# Adafruit_5x5_NeoPixel_Grid_BFF.net
KiCad netlist of a schematic drawn in EAGLE
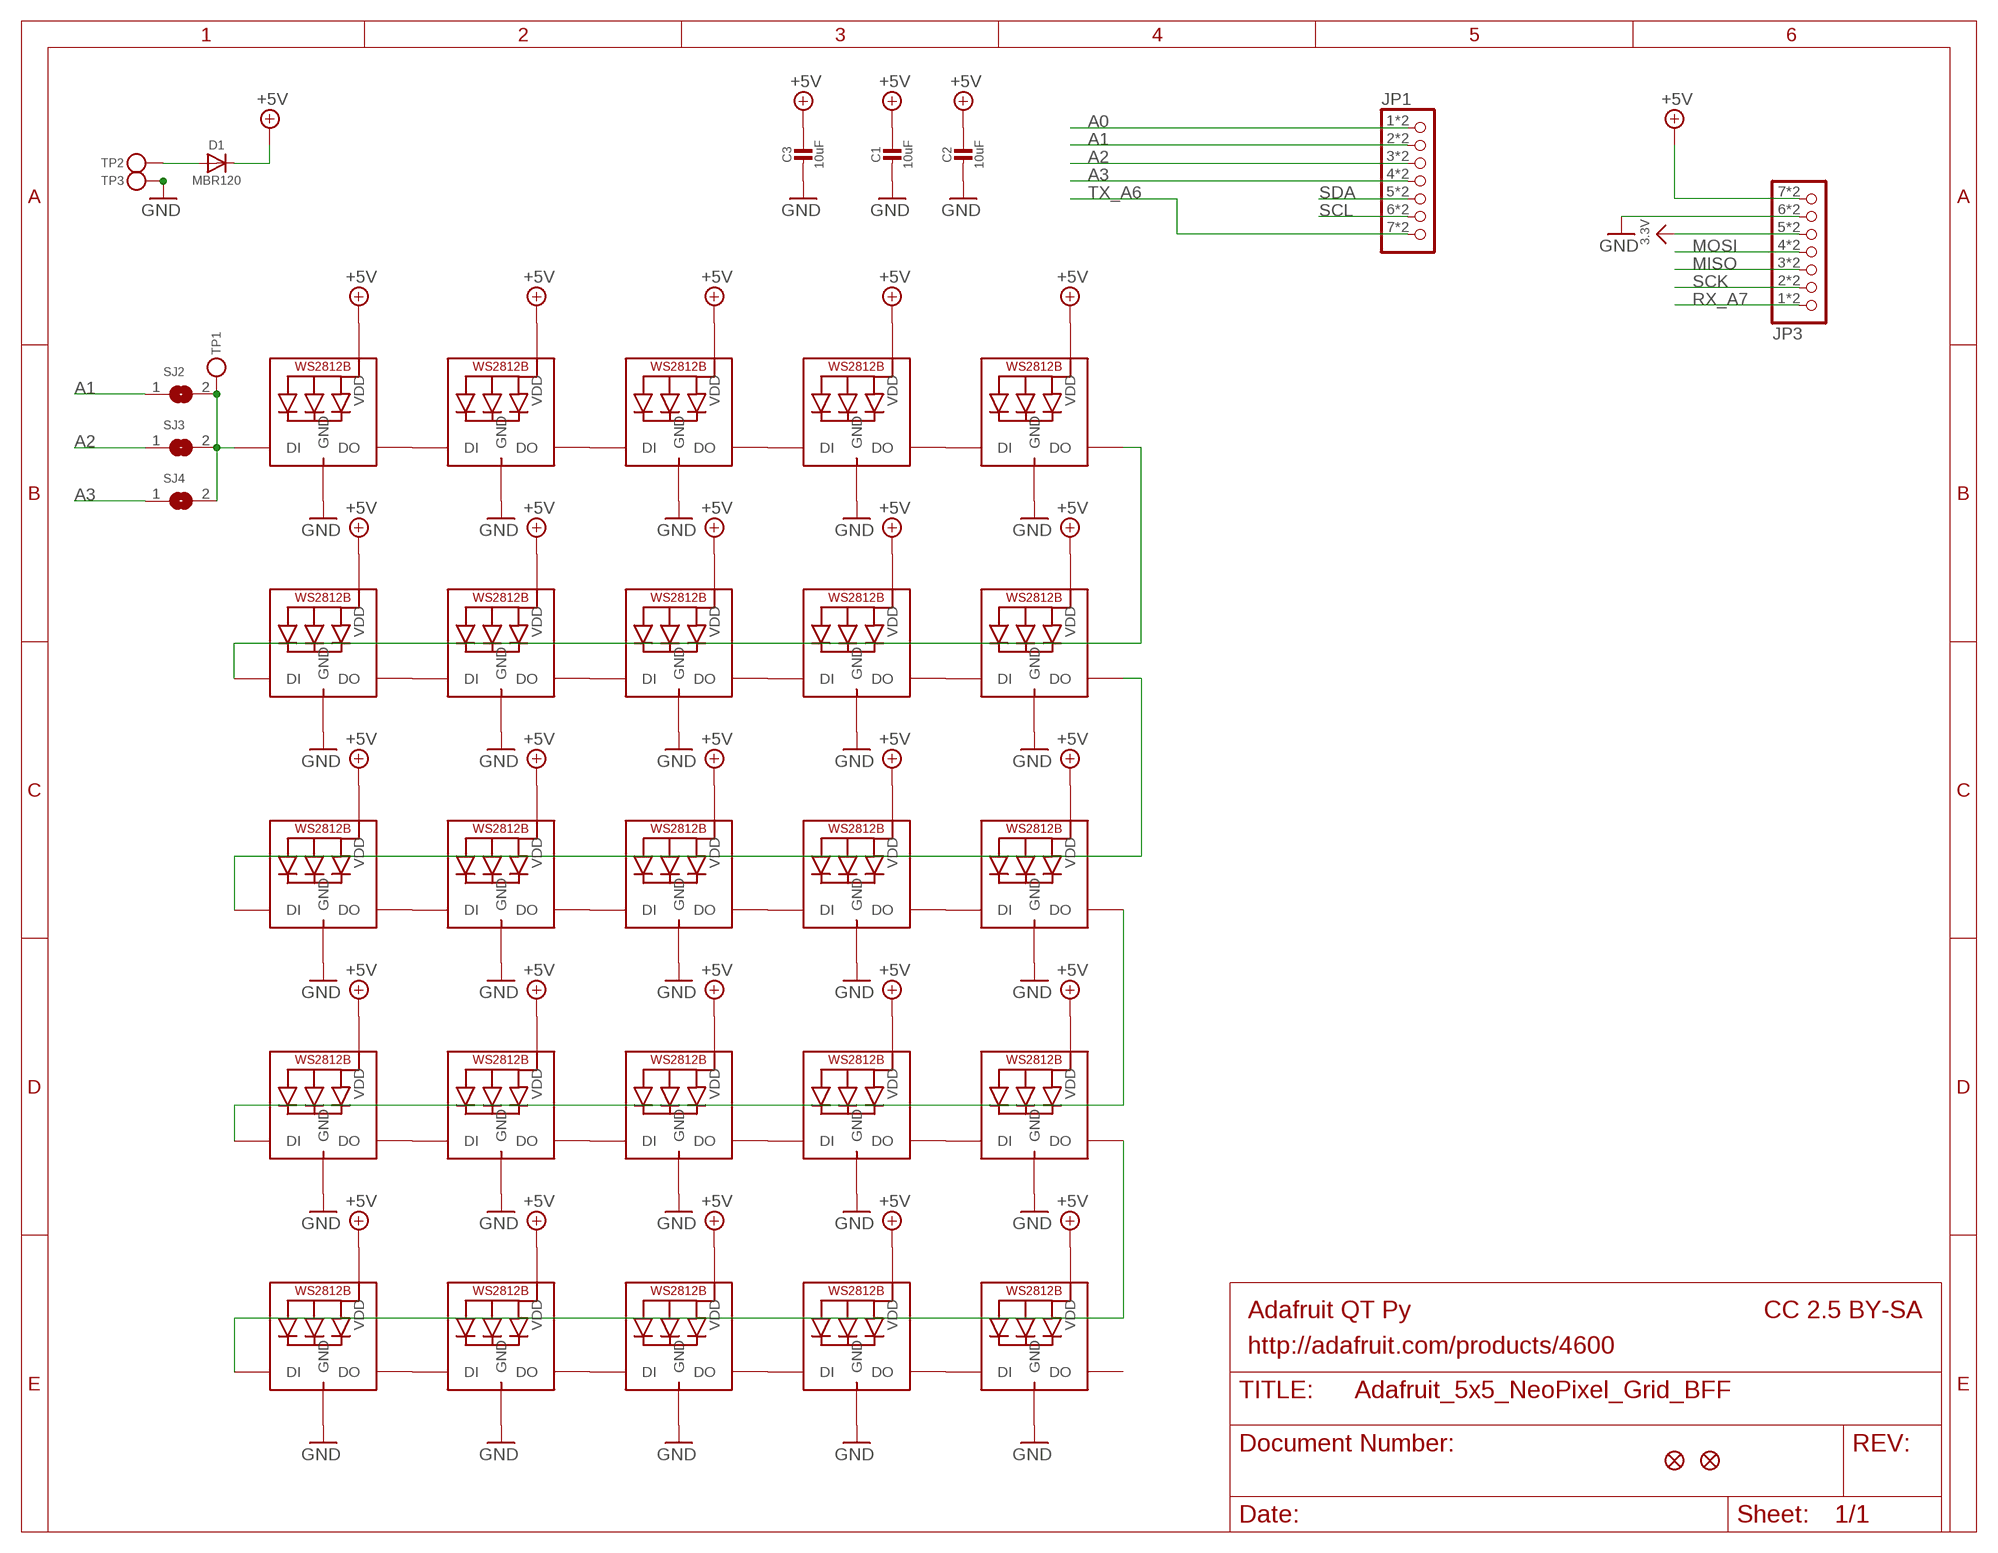
[diagram p0: schematic, sheet 1]

(export (version "E")
  (design (tool "Eeschema 10.0.6"))
  (components
    (comp (ref "C1")
      (value "10uF")
      (footprint "eagle-import:0603-NO")
      (libsource (lib "eagle-import") (part "CAP_CERAMIC0603_NO"))
    )
    (comp (ref "C2")
      (value "10uF")
      (footprint "eagle-import:0603-NO")
      (libsource (lib "eagle-import") (part "CAP_CERAMIC0603_NO"))
    )
    (comp (ref "C3")
      (value "10uF")
      (footprint "eagle-import:0603-NO")
      (libsource (lib "eagle-import") (part "CAP_CERAMIC0603_NO"))
    )
    (comp (ref "D1")
      (value "MBR120")
      (footprint "eagle-import:SOD-123")
      (libsource (lib "eagle-import") (part "DIODESOD-123"))
    )
    (comp (ref "JP1")
      (value "HEADER-1X7_CASTEL")
      (footprint "eagle-import:1X07_CASTEL")
      (libsource (lib "eagle-import") (part "HEADER-1X7_CASTEL"))
    )
    (comp (ref "JP3")
      (value "HEADER-1X7_CASTEL")
      (footprint "eagle-import:1X07_CASTEL")
      (libsource (lib "eagle-import") (part "HEADER-1X7_CASTEL"))
    )
    (comp (ref "LED1")
      (value "WS2812B_SK6805_1515")
      (footprint "eagle-import:SK6805_1515")
      (libsource (lib "eagle-import") (part "WS2812B_SK6805_1515"))
    )
    (comp (ref "LED2")
      (value "WS2812B_SK6805_1515")
      (footprint "eagle-import:SK6805_1515")
      (libsource (lib "eagle-import") (part "WS2812B_SK6805_1515"))
    )
    (comp (ref "LED3")
      (value "WS2812B_SK6805_1515")
      (footprint "eagle-import:SK6805_1515")
      (libsource (lib "eagle-import") (part "WS2812B_SK6805_1515"))
    )
    (comp (ref "LED4")
      (value "WS2812B_SK6805_1515")
      (footprint "eagle-import:SK6805_1515")
      (libsource (lib "eagle-import") (part "WS2812B_SK6805_1515"))
    )
    (comp (ref "LED5")
      (value "WS2812B_SK6805_1515")
      (footprint "eagle-import:SK6805_1515")
      (libsource (lib "eagle-import") (part "WS2812B_SK6805_1515"))
    )
    (comp (ref "LED6")
      (value "WS2812B_SK6805_1515")
      (footprint "eagle-import:SK6805_1515")
      (libsource (lib "eagle-import") (part "WS2812B_SK6805_1515"))
    )
    (comp (ref "LED7")
      (value "WS2812B_SK6805_1515")
      (footprint "eagle-import:SK6805_1515")
      (libsource (lib "eagle-import") (part "WS2812B_SK6805_1515"))
    )
    (comp (ref "LED8")
      (value "WS2812B_SK6805_1515")
      (footprint "eagle-import:SK6805_1515")
      (libsource (lib "eagle-import") (part "WS2812B_SK6805_1515"))
    )
    (comp (ref "LED9")
      (value "WS2812B_SK6805_1515")
      (footprint "eagle-import:SK6805_1515")
      (libsource (lib "eagle-import") (part "WS2812B_SK6805_1515"))
    )
    (comp (ref "LED10")
      (value "WS2812B_SK6805_1515")
      (footprint "eagle-import:SK6805_1515")
      (libsource (lib "eagle-import") (part "WS2812B_SK6805_1515"))
    )
    (comp (ref "LED11")
      (value "WS2812B_SK6805_1515")
      (footprint "eagle-import:SK6805_1515")
      (libsource (lib "eagle-import") (part "WS2812B_SK6805_1515"))
    )
    (comp (ref "LED12")
      (value "WS2812B_SK6805_1515")
      (footprint "eagle-import:SK6805_1515")
      (libsource (lib "eagle-import") (part "WS2812B_SK6805_1515"))
    )
    (comp (ref "LED13")
      (value "WS2812B_SK6805_1515")
      (footprint "eagle-import:SK6805_1515")
      (libsource (lib "eagle-import") (part "WS2812B_SK6805_1515"))
    )
    (comp (ref "LED14")
      (value "WS2812B_SK6805_1515")
      (footprint "eagle-import:SK6805_1515")
      (libsource (lib "eagle-import") (part "WS2812B_SK6805_1515"))
    )
    (comp (ref "LED15")
      (value "WS2812B_SK6805_1515")
      (footprint "eagle-import:SK6805_1515")
      (libsource (lib "eagle-import") (part "WS2812B_SK6805_1515"))
    )
    (comp (ref "LED16")
      (value "WS2812B_SK6805_1515")
      (footprint "eagle-import:SK6805_1515")
      (libsource (lib "eagle-import") (part "WS2812B_SK6805_1515"))
    )
    (comp (ref "LED17")
      (value "WS2812B_SK6805_1515")
      (footprint "eagle-import:SK6805_1515")
      (libsource (lib "eagle-import") (part "WS2812B_SK6805_1515"))
    )
    (comp (ref "LED18")
      (value "WS2812B_SK6805_1515")
      (footprint "eagle-import:SK6805_1515")
      (libsource (lib "eagle-import") (part "WS2812B_SK6805_1515"))
    )
    (comp (ref "LED19")
      (value "WS2812B_SK6805_1515")
      (footprint "eagle-import:SK6805_1515")
      (libsource (lib "eagle-import") (part "WS2812B_SK6805_1515"))
    )
    (comp (ref "LED20")
      (value "WS2812B_SK6805_1515")
      (footprint "eagle-import:SK6805_1515")
      (libsource (lib "eagle-import") (part "WS2812B_SK6805_1515"))
    )
    (comp (ref "LED21")
      (value "WS2812B_SK6805_1515")
      (footprint "eagle-import:SK6805_1515")
      (libsource (lib "eagle-import") (part "WS2812B_SK6805_1515"))
    )
    (comp (ref "LED22")
      (value "WS2812B_SK6805_1515")
      (footprint "eagle-import:SK6805_1515")
      (libsource (lib "eagle-import") (part "WS2812B_SK6805_1515"))
    )
    (comp (ref "LED23")
      (value "WS2812B_SK6805_1515")
      (footprint "eagle-import:SK6805_1515")
      (libsource (lib "eagle-import") (part "WS2812B_SK6805_1515"))
    )
    (comp (ref "LED24")
      (value "WS2812B_SK6805_1515")
      (footprint "eagle-import:SK6805_1515")
      (libsource (lib "eagle-import") (part "WS2812B_SK6805_1515"))
    )
    (comp (ref "LED25")
      (value "WS2812B_SK6805_1515")
      (footprint "eagle-import:SK6805_1515")
      (libsource (lib "eagle-import") (part "WS2812B_SK6805_1515"))
    )
    (comp (ref "SJ2")
      (value "SOLDERJUMPER")
      (footprint "eagle-import:SOLDERJUMPER_ARROW_NOPASTE")
      (libsource (lib "eagle-import") (part "SOLDERJUMPER"))
    )
    (comp (ref "SJ3")
      (value "SOLDERJUMPER")
      (footprint "eagle-import:SOLDERJUMPER_ARROW_NOPASTE")
      (libsource (lib "eagle-import") (part "SOLDERJUMPER"))
    )
    (comp (ref "SJ4")
      (value "SOLDERJUMPERCLOSED")
      (footprint "eagle-import:SOLDERJUMPER_CLOSEDWIRE")
      (libsource (lib "eagle-import") (part "SOLDERJUMPERCLOSED"))
    )
    (comp (ref "TP1")
      (value "TESTPOINT_1X3")
      (footprint "eagle-import:TESTPOINT_RECT_1X3MM")
      (libsource (lib "eagle-import") (part "TESTPOINT_1X3"))
    )
    (comp (ref "TP2")
      (value "TESTPOINT_PLUS13")
      (footprint "eagle-import:TESTPOINT_PLUS_1X3MM")
      (libsource (lib "eagle-import") (part "TESTPOINT_PLUS13"))
    )
    (comp (ref "TP3")
      (value "TESTPOINT_MINUS")
      (footprint "eagle-import:TESTPOINT_MINUS_1X3MM")
      (libsource (lib "eagle-import") (part "TESTPOINT_MINUS"))
    )
    (comp (ref "U$6")
      (value "FIDUCIAL_1MM")
      (footprint "eagle-import:FIDUCIAL_1MM")
      (libsource (lib "eagle-import") (part "FIDUCIAL_1MM"))
    )
    (comp (ref "U$8")
      (value "FIDUCIAL_1MM")
      (footprint "eagle-import:FIDUCIAL_1MM")
      (libsource (lib "eagle-import") (part "FIDUCIAL_1MM"))
    )
  )
  (nets
    (net (code "1") (name "+5V") (class "Default")
      (node (ref "C1") (pin "1") (pinfunction "1_1") (pintype "passive"))
      (node (ref "C2") (pin "1") (pinfunction "1_1") (pintype "passive"))
      (node (ref "C3") (pin "1") (pinfunction "1_1") (pintype "passive"))
      (node (ref "D1") (pin "C") (pinfunction "C_C") (pintype "passive"))
      (node (ref "JP3") (pin "7") (pinfunction "7_7") (pintype "passive"))
      (node (ref "JP3") (pin "7C") (pinfunction "7_7C") (pintype "passive"))
      (node (ref "LED1") (pin "2") (pinfunction "VDD_2") (pintype "power_in"))
      (node (ref "LED10") (pin "2") (pinfunction "VDD_2") (pintype "power_in"))
      (node (ref "LED11") (pin "2") (pinfunction "VDD_2") (pintype "power_in"))
      (node (ref "LED12") (pin "2") (pinfunction "VDD_2") (pintype "power_in"))
      (node (ref "LED13") (pin "2") (pinfunction "VDD_2") (pintype "power_in"))
      (node (ref "LED14") (pin "2") (pinfunction "VDD_2") (pintype "power_in"))
      (node (ref "LED15") (pin "2") (pinfunction "VDD_2") (pintype "power_in"))
      (node (ref "LED16") (pin "2") (pinfunction "VDD_2") (pintype "power_in"))
      (node (ref "LED17") (pin "2") (pinfunction "VDD_2") (pintype "power_in"))
      (node (ref "LED18") (pin "2") (pinfunction "VDD_2") (pintype "power_in"))
      (node (ref "LED19") (pin "2") (pinfunction "VDD_2") (pintype "power_in"))
      (node (ref "LED2") (pin "2") (pinfunction "VDD_2") (pintype "power_in"))
      (node (ref "LED20") (pin "2") (pinfunction "VDD_2") (pintype "power_in"))
      (node (ref "LED21") (pin "2") (pinfunction "VDD_2") (pintype "power_in"))
      (node (ref "LED22") (pin "2") (pinfunction "VDD_2") (pintype "power_in"))
      (node (ref "LED23") (pin "2") (pinfunction "VDD_2") (pintype "power_in"))
      (node (ref "LED24") (pin "2") (pinfunction "VDD_2") (pintype "power_in"))
      (node (ref "LED25") (pin "2") (pinfunction "VDD_2") (pintype "power_in"))
      (node (ref "LED3") (pin "2") (pinfunction "VDD_2") (pintype "power_in"))
      (node (ref "LED4") (pin "2") (pinfunction "VDD_2") (pintype "power_in"))
      (node (ref "LED5") (pin "2") (pinfunction "VDD_2") (pintype "power_in"))
      (node (ref "LED6") (pin "2") (pinfunction "VDD_2") (pintype "power_in"))
      (node (ref "LED7") (pin "2") (pinfunction "VDD_2") (pintype "power_in"))
      (node (ref "LED8") (pin "2") (pinfunction "VDD_2") (pintype "power_in"))
      (node (ref "LED9") (pin "2") (pinfunction "VDD_2") (pintype "power_in"))
    )
    (net (code "2") (name "/A0") (class "Default")
      (node (ref "JP1") (pin "1") (pinfunction "1_1") (pintype "passive"))
      (node (ref "JP1") (pin "1C") (pinfunction "1_1C") (pintype "passive"))
    )
    (net (code "3") (name "/A1") (class "Default")
      (node (ref "JP1") (pin "2") (pinfunction "2_2") (pintype "passive"))
      (node (ref "JP1") (pin "2C") (pinfunction "2_2C") (pintype "passive"))
      (node (ref "SJ2") (pin "1") (pinfunction "1_1") (pintype "passive"))
    )
    (net (code "4") (name "/A2") (class "Default")
      (node (ref "JP1") (pin "3") (pinfunction "3_3") (pintype "passive"))
      (node (ref "JP1") (pin "3C") (pinfunction "3_3C") (pintype "passive"))
      (node (ref "SJ3") (pin "1") (pinfunction "1_1") (pintype "passive"))
    )
    (net (code "5") (name "/A3") (class "Default")
      (node (ref "JP1") (pin "4") (pinfunction "4_4") (pintype "passive"))
      (node (ref "JP1") (pin "4C") (pinfunction "4_4C") (pintype "passive"))
      (node (ref "SJ4") (pin "1") (pinfunction "1_1") (pintype "passive"))
    )
    (net (code "6") (name "/MISO") (class "Default")
      (node (ref "JP3") (pin "3") (pinfunction "3_3") (pintype "passive"))
      (node (ref "JP3") (pin "3C") (pinfunction "3_3C") (pintype "passive"))
    )
    (net (code "7") (name "/MOSI") (class "Default")
      (node (ref "JP3") (pin "4") (pinfunction "4_4") (pintype "passive"))
      (node (ref "JP3") (pin "4C") (pinfunction "4_4C") (pintype "passive"))
    )
    (net (code "8") (name "/RX_A7") (class "Default")
      (node (ref "JP3") (pin "1") (pinfunction "1_1") (pintype "passive"))
      (node (ref "JP3") (pin "1C") (pinfunction "1_1C") (pintype "passive"))
    )
    (net (code "9") (name "/SCK") (class "Default")
      (node (ref "JP3") (pin "2") (pinfunction "2_2") (pintype "passive"))
      (node (ref "JP3") (pin "2C") (pinfunction "2_2C") (pintype "passive"))
    )
    (net (code "10") (name "/SCL") (class "Default")
      (node (ref "JP1") (pin "6") (pinfunction "6_6") (pintype "passive"))
      (node (ref "JP1") (pin "6C") (pinfunction "6_6C") (pintype "passive"))
    )
    (net (code "11") (name "/SDA") (class "Default")
      (node (ref "JP1") (pin "5") (pinfunction "5_5") (pintype "passive"))
      (node (ref "JP1") (pin "5C") (pinfunction "5_5C") (pintype "passive"))
    )
    (net (code "12") (name "/TX_A6") (class "Default")
      (node (ref "JP1") (pin "7") (pinfunction "7_7") (pintype "passive"))
      (node (ref "JP1") (pin "7C") (pinfunction "7_7C") (pintype "passive"))
    )
    (net (code "13") (name "3.3V") (class "Default")
      (node (ref "JP3") (pin "5") (pinfunction "5_5") (pintype "passive"))
      (node (ref "JP3") (pin "5C") (pinfunction "5_5C") (pintype "passive"))
    )
    (net (code "14") (name "GND") (class "Default")
      (node (ref "C1") (pin "2") (pinfunction "2_2") (pintype "passive"))
      (node (ref "C2") (pin "2") (pinfunction "2_2") (pintype "passive"))
      (node (ref "C3") (pin "2") (pinfunction "2_2") (pintype "passive"))
      (node (ref "JP3") (pin "6") (pinfunction "6_6") (pintype "passive"))
      (node (ref "JP3") (pin "6C") (pinfunction "6_6C") (pintype "passive"))
      (node (ref "LED1") (pin "4") (pinfunction "GND_4") (pintype "power_in"))
      (node (ref "LED10") (pin "4") (pinfunction "GND_4") (pintype "power_in"))
      (node (ref "LED11") (pin "4") (pinfunction "GND_4") (pintype "power_in"))
      (node (ref "LED12") (pin "4") (pinfunction "GND_4") (pintype "power_in"))
      (node (ref "LED13") (pin "4") (pinfunction "GND_4") (pintype "power_in"))
      (node (ref "LED14") (pin "4") (pinfunction "GND_4") (pintype "power_in"))
      (node (ref "LED15") (pin "4") (pinfunction "GND_4") (pintype "power_in"))
      (node (ref "LED16") (pin "4") (pinfunction "GND_4") (pintype "power_in"))
      (node (ref "LED17") (pin "4") (pinfunction "GND_4") (pintype "power_in"))
      (node (ref "LED18") (pin "4") (pinfunction "GND_4") (pintype "power_in"))
      (node (ref "LED19") (pin "4") (pinfunction "GND_4") (pintype "power_in"))
      (node (ref "LED2") (pin "4") (pinfunction "GND_4") (pintype "power_in"))
      (node (ref "LED20") (pin "4") (pinfunction "GND_4") (pintype "power_in"))
      (node (ref "LED21") (pin "4") (pinfunction "GND_4") (pintype "power_in"))
      (node (ref "LED22") (pin "4") (pinfunction "GND_4") (pintype "power_in"))
      (node (ref "LED23") (pin "4") (pinfunction "GND_4") (pintype "power_in"))
      (node (ref "LED24") (pin "4") (pinfunction "GND_4") (pintype "power_in"))
      (node (ref "LED25") (pin "4") (pinfunction "GND_4") (pintype "power_in"))
      (node (ref "LED3") (pin "4") (pinfunction "GND_4") (pintype "power_in"))
      (node (ref "LED4") (pin "4") (pinfunction "GND_4") (pintype "power_in"))
      (node (ref "LED5") (pin "4") (pinfunction "GND_4") (pintype "power_in"))
      (node (ref "LED6") (pin "4") (pinfunction "GND_4") (pintype "power_in"))
      (node (ref "LED7") (pin "4") (pinfunction "GND_4") (pintype "power_in"))
      (node (ref "LED8") (pin "4") (pinfunction "GND_4") (pintype "power_in"))
      (node (ref "LED9") (pin "4") (pinfunction "GND_4") (pintype "power_in"))
      (node (ref "TP3") (pin "P$1") (pinfunction "P$1_P$1") (pintype "bidirectional"))
    )
    (net (code "15") (name "Net-(D1-PadA)") (class "Default")
      (node (ref "D1") (pin "A") (pinfunction "A_A") (pintype "passive"))
      (node (ref "TP2") (pin "P$1") (pinfunction "P$1_P$1") (pintype "bidirectional"))
    )
    (net (code "16") (name "Net-(LED1-DI)") (class "Default")
      (node (ref "LED1") (pin "1") (pinfunction "DI_1") (pintype "input"))
      (node (ref "SJ2") (pin "2") (pinfunction "2_2") (pintype "passive"))
      (node (ref "SJ3") (pin "2") (pinfunction "2_2") (pintype "passive"))
      (node (ref "SJ4") (pin "2") (pinfunction "2_2") (pintype "passive"))
      (node (ref "TP1") (pin "P$1") (pinfunction "P$1_P$1") (pintype "bidirectional"))
    )
    (net (code "17") (name "Net-(LED1-DO)") (class "Default")
      (node (ref "LED1") (pin "3") (pinfunction "DO_3") (pintype "output"))
      (node (ref "LED2") (pin "1") (pinfunction "DI_1") (pintype "input"))
    )
    (net (code "18") (name "Net-(LED2-DO)") (class "Default")
      (node (ref "LED2") (pin "3") (pinfunction "DO_3") (pintype "output"))
      (node (ref "LED3") (pin "1") (pinfunction "DI_1") (pintype "input"))
    )
    (net (code "19") (name "Net-(LED3-DO)") (class "Default")
      (node (ref "LED3") (pin "3") (pinfunction "DO_3") (pintype "output"))
      (node (ref "LED4") (pin "1") (pinfunction "DI_1") (pintype "input"))
    )
    (net (code "20") (name "Net-(LED4-DO)") (class "Default")
      (node (ref "LED4") (pin "3") (pinfunction "DO_3") (pintype "output"))
      (node (ref "LED5") (pin "1") (pinfunction "DI_1") (pintype "input"))
    )
    (net (code "21") (name "Net-(LED5-DO)") (class "Default")
      (node (ref "LED5") (pin "3") (pinfunction "DO_3") (pintype "output"))
      (node (ref "LED6") (pin "1") (pinfunction "DI_1") (pintype "input"))
    )
    (net (code "22") (name "Net-(LED6-DO)") (class "Default")
      (node (ref "LED6") (pin "3") (pinfunction "DO_3") (pintype "output"))
      (node (ref "LED7") (pin "1") (pinfunction "DI_1") (pintype "input"))
    )
    (net (code "23") (name "Net-(LED7-DO)") (class "Default")
      (node (ref "LED7") (pin "3") (pinfunction "DO_3") (pintype "output"))
      (node (ref "LED8") (pin "1") (pinfunction "DI_1") (pintype "input"))
    )
    (net (code "24") (name "Net-(LED8-DO)") (class "Default")
      (node (ref "LED8") (pin "3") (pinfunction "DO_3") (pintype "output"))
      (node (ref "LED9") (pin "1") (pinfunction "DI_1") (pintype "input"))
    )
    (net (code "25") (name "Net-(LED10-DI)") (class "Default")
      (node (ref "LED10") (pin "1") (pinfunction "DI_1") (pintype "input"))
      (node (ref "LED9") (pin "3") (pinfunction "DO_3") (pintype "output"))
    )
    (net (code "26") (name "Net-(LED10-DO)") (class "Default")
      (node (ref "LED10") (pin "3") (pinfunction "DO_3") (pintype "output"))
      (node (ref "LED11") (pin "1") (pinfunction "DI_1") (pintype "input"))
    )
    (net (code "27") (name "Net-(LED11-DO)") (class "Default")
      (node (ref "LED11") (pin "3") (pinfunction "DO_3") (pintype "output"))
      (node (ref "LED12") (pin "1") (pinfunction "DI_1") (pintype "input"))
    )
    (net (code "28") (name "Net-(LED12-DO)") (class "Default")
      (node (ref "LED12") (pin "3") (pinfunction "DO_3") (pintype "output"))
      (node (ref "LED13") (pin "1") (pinfunction "DI_1") (pintype "input"))
    )
    (net (code "29") (name "Net-(LED13-DO)") (class "Default")
      (node (ref "LED13") (pin "3") (pinfunction "DO_3") (pintype "output"))
      (node (ref "LED14") (pin "1") (pinfunction "DI_1") (pintype "input"))
    )
    (net (code "30") (name "Net-(LED14-DO)") (class "Default")
      (node (ref "LED14") (pin "3") (pinfunction "DO_3") (pintype "output"))
      (node (ref "LED15") (pin "1") (pinfunction "DI_1") (pintype "input"))
    )
    (net (code "31") (name "Net-(LED15-DO)") (class "Default")
      (node (ref "LED15") (pin "3") (pinfunction "DO_3") (pintype "output"))
      (node (ref "LED16") (pin "1") (pinfunction "DI_1") (pintype "input"))
    )
    (net (code "32") (name "Net-(LED16-DO)") (class "Default")
      (node (ref "LED16") (pin "3") (pinfunction "DO_3") (pintype "output"))
      (node (ref "LED17") (pin "1") (pinfunction "DI_1") (pintype "input"))
    )
    (net (code "33") (name "Net-(LED17-DO)") (class "Default")
      (node (ref "LED17") (pin "3") (pinfunction "DO_3") (pintype "output"))
      (node (ref "LED18") (pin "1") (pinfunction "DI_1") (pintype "input"))
    )
    (net (code "34") (name "Net-(LED18-DO)") (class "Default")
      (node (ref "LED18") (pin "3") (pinfunction "DO_3") (pintype "output"))
      (node (ref "LED19") (pin "1") (pinfunction "DI_1") (pintype "input"))
    )
    (net (code "35") (name "Net-(LED19-DO)") (class "Default")
      (node (ref "LED19") (pin "3") (pinfunction "DO_3") (pintype "output"))
      (node (ref "LED20") (pin "1") (pinfunction "DI_1") (pintype "input"))
    )
    (net (code "36") (name "Net-(LED20-DO)") (class "Default")
      (node (ref "LED20") (pin "3") (pinfunction "DO_3") (pintype "output"))
      (node (ref "LED21") (pin "1") (pinfunction "DI_1") (pintype "input"))
    )
    (net (code "37") (name "Net-(LED21-DO)") (class "Default")
      (node (ref "LED21") (pin "3") (pinfunction "DO_3") (pintype "output"))
      (node (ref "LED22") (pin "1") (pinfunction "DI_1") (pintype "input"))
    )
    (net (code "38") (name "Net-(LED22-DO)") (class "Default")
      (node (ref "LED22") (pin "3") (pinfunction "DO_3") (pintype "output"))
      (node (ref "LED23") (pin "1") (pinfunction "DI_1") (pintype "input"))
    )
    (net (code "39") (name "Net-(LED23-DO)") (class "Default")
      (node (ref "LED23") (pin "3") (pinfunction "DO_3") (pintype "output"))
      (node (ref "LED24") (pin "1") (pinfunction "DI_1") (pintype "input"))
    )
    (net (code "40") (name "Net-(LED24-DO)") (class "Default")
      (node (ref "LED24") (pin "3") (pinfunction "DO_3") (pintype "output"))
      (node (ref "LED25") (pin "1") (pinfunction "DI_1") (pintype "input"))
    )
    (net (code "41") (name "unconnected-(LED25-DO-Pad3)") (class "Default")
      (node (ref "LED25") (pin "3") (pinfunction "DO_3") (pintype "output"))
    )
  )
)
